# 464342_21-005_3_2.net
KiCad netlist of a schematic drawn in Altium Designer
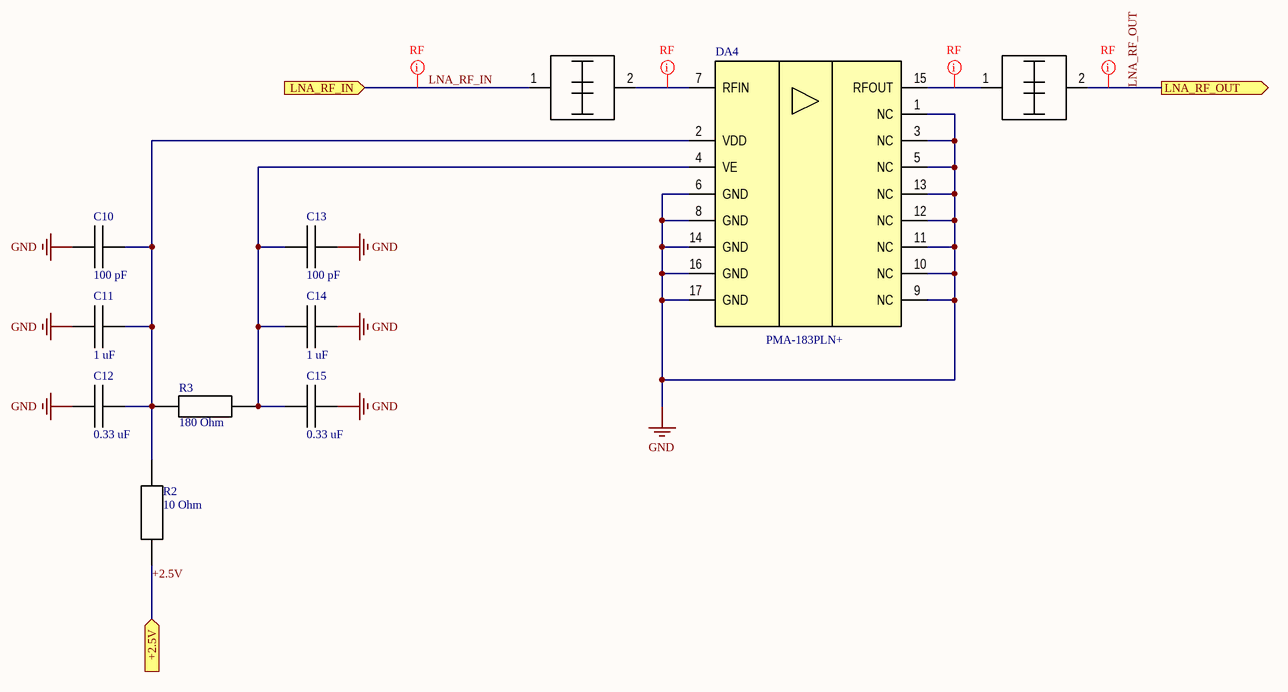
[diagram p0: МПСУ.464342.21-005 Э3 Лист2.SchDoc]

(export (version "E")
  (design (tool "Eeschema 10.0.6"))
  (components
    (comp (ref "C10")
      (value "100 pF")
      (footprint "CAPC100X50X55L20N")
      (description "Capacitor, generic")
      (libsource (lib "Discrete") (part "Capacitor"))
    )
    (comp (ref "C11")
      (value "1 uF")
      (footprint "CAPC160X80X90L30N")
      (description "Capacitor, generic")
      (libsource (lib "Discrete") (part "Capacitor"))
    )
    (comp (ref "C12")
      (value "0.33 uF")
      (footprint "CAPC200X125X95L50N")
      (description "Capacitor, generic")
      (libsource (lib "Discrete") (part "Capacitor"))
    )
    (comp (ref "C13")
      (value "100 pF")
      (footprint "CAPC100X50X55L20N")
      (description "Capacitor, generic")
      (libsource (lib "Discrete") (part "Capacitor"))
    )
    (comp (ref "C14")
      (value "1 uF")
      (footprint "CAPC160X80X90L30N")
      (description "Capacitor, generic")
      (libsource (lib "Discrete") (part "Capacitor"))
    )
    (comp (ref "C15")
      (value "0.33 uF")
      (footprint "CAPC200X125X95L50N")
      (description "Capacitor, generic")
      (libsource (lib "Discrete") (part "Capacitor"))
    )
    (comp (ref "DA4")
      (value "PMA-183PLN+")
      (footprint "JV2579")
      (description "SMT Low Noise Amplifier, 6000 - 18000 MHz, 50Ω")
      (fields (field (name "MANUFACTURER") "Mini-Circuits"))
      (libsource (lib "Amplifiers") (part "PMA-183PLN+"))
    )
    (comp (ref "R2")
      (value "10 Ohm")
      (footprint "RESC100X50X40L25N")
      (description "Resistor, generic")
      (libsource (lib "") (part "Resistor_1"))
    )
    (comp (ref "R3")
      (value "180 Ohm")
      (footprint "RESC100X50X40L25N")
      (description "Resistor, generic")
      (libsource (lib "Discrete") (part "Resistor"))
    )
    (comp (ref "W4")
      (value "Matching")
      (footprint "MATCHING_LNA_IN")
      (description "Matching MTEE")
      (libsource (lib "Microstrip") (part "Matching_1"))
    )
    (comp (ref "W5")
      (value "Matching")
      (footprint "MATCHING_LNA_OUT")
      (description "Matching MTEE")
      (libsource (lib "Microstrip") (part "Matching_1"))
    )
  )
  (nets
    (net (code "1") (name "/+2.5V") (class "Default")
      (node (ref "R2") (pin "1") (pinfunction "1_1") (pintype "passive"))
    )
    (net (code "2") (name "/LNA_RF_IN") (class "Default")
      (node (ref "W4") (pin "1") (pinfunction "1_1") (pintype "passive"))
    )
    (net (code "3") (name "/LNA_RF_OUT") (class "Default")
      (node (ref "W5") (pin "2") (pinfunction "2_2") (pintype "passive"))
    )
    (net (code "4") (name "GND") (class "Default")
      (node (ref "C10") (pin "1") (pinfunction "1_1") (pintype "passive"))
      (node (ref "C11") (pin "1") (pinfunction "1_1") (pintype "passive"))
      (node (ref "C12") (pin "1") (pinfunction "1_1") (pintype "passive"))
      (node (ref "C13") (pin "2") (pinfunction "2_2") (pintype "passive"))
      (node (ref "C14") (pin "2") (pinfunction "2_2") (pintype "passive"))
      (node (ref "C15") (pin "2") (pinfunction "2_2") (pintype "passive"))
      (node (ref "DA4") (pin "1") (pinfunction "NC_1") (pintype "passive"))
      (node (ref "DA4") (pin "10") (pinfunction "NC_10") (pintype "passive"))
      (node (ref "DA4") (pin "11") (pinfunction "NC_11") (pintype "passive"))
      (node (ref "DA4") (pin "12") (pinfunction "NC_12") (pintype "passive"))
      (node (ref "DA4") (pin "13") (pinfunction "NC_13") (pintype "passive"))
      (node (ref "DA4") (pin "14") (pinfunction "GND_14") (pintype "passive"))
      (node (ref "DA4") (pin "16") (pinfunction "GND_16") (pintype "passive"))
      (node (ref "DA4") (pin "17") (pinfunction "GND_17") (pintype "passive"))
      (node (ref "DA4") (pin "3") (pinfunction "NC_3") (pintype "passive"))
      (node (ref "DA4") (pin "5") (pinfunction "NC_5") (pintype "passive"))
      (node (ref "DA4") (pin "6") (pinfunction "GND_6") (pintype "passive"))
      (node (ref "DA4") (pin "8") (pinfunction "GND_8") (pintype "passive"))
      (node (ref "DA4") (pin "9") (pinfunction "NC_9") (pintype "passive"))
    )
    (net (code "5") (name "Net-(DA4-RFIN)") (class "Default")
      (node (ref "DA4") (pin "7") (pinfunction "RFIN_7") (pintype "passive"))
      (node (ref "W4") (pin "2") (pinfunction "2_2") (pintype "passive"))
    )
    (net (code "6") (name "Net-(DA4-RFOUT)") (class "Default")
      (node (ref "DA4") (pin "15") (pinfunction "RFOUT_15") (pintype "passive"))
      (node (ref "W5") (pin "1") (pinfunction "1_1") (pintype "passive"))
    )
    (net (code "7") (name "Net-(DA4-VDD)") (class "Default")
      (node (ref "C10") (pin "2") (pinfunction "2_2") (pintype "passive"))
      (node (ref "C11") (pin "2") (pinfunction "2_2") (pintype "passive"))
      (node (ref "C12") (pin "2") (pinfunction "2_2") (pintype "passive"))
      (node (ref "DA4") (pin "2") (pinfunction "VDD_2") (pintype "passive"))
      (node (ref "R2") (pin "2") (pinfunction "2_2") (pintype "passive"))
      (node (ref "R3") (pin "1") (pinfunction "1_1") (pintype "passive"))
    )
    (net (code "8") (name "Net-(DA4-VE)") (class "Default")
      (node (ref "C13") (pin "1") (pinfunction "1_1") (pintype "passive"))
      (node (ref "C14") (pin "1") (pinfunction "1_1") (pintype "passive"))
      (node (ref "C15") (pin "1") (pinfunction "1_1") (pintype "passive"))
      (node (ref "DA4") (pin "4") (pinfunction "VE_4") (pintype "passive"))
      (node (ref "R3") (pin "2") (pinfunction "2_2") (pintype "passive"))
    )
  )
)
